# RPS_ARMOR_PCB_2022_V1_1.net
KiCad netlist of a schematic drawn in Altium Designer
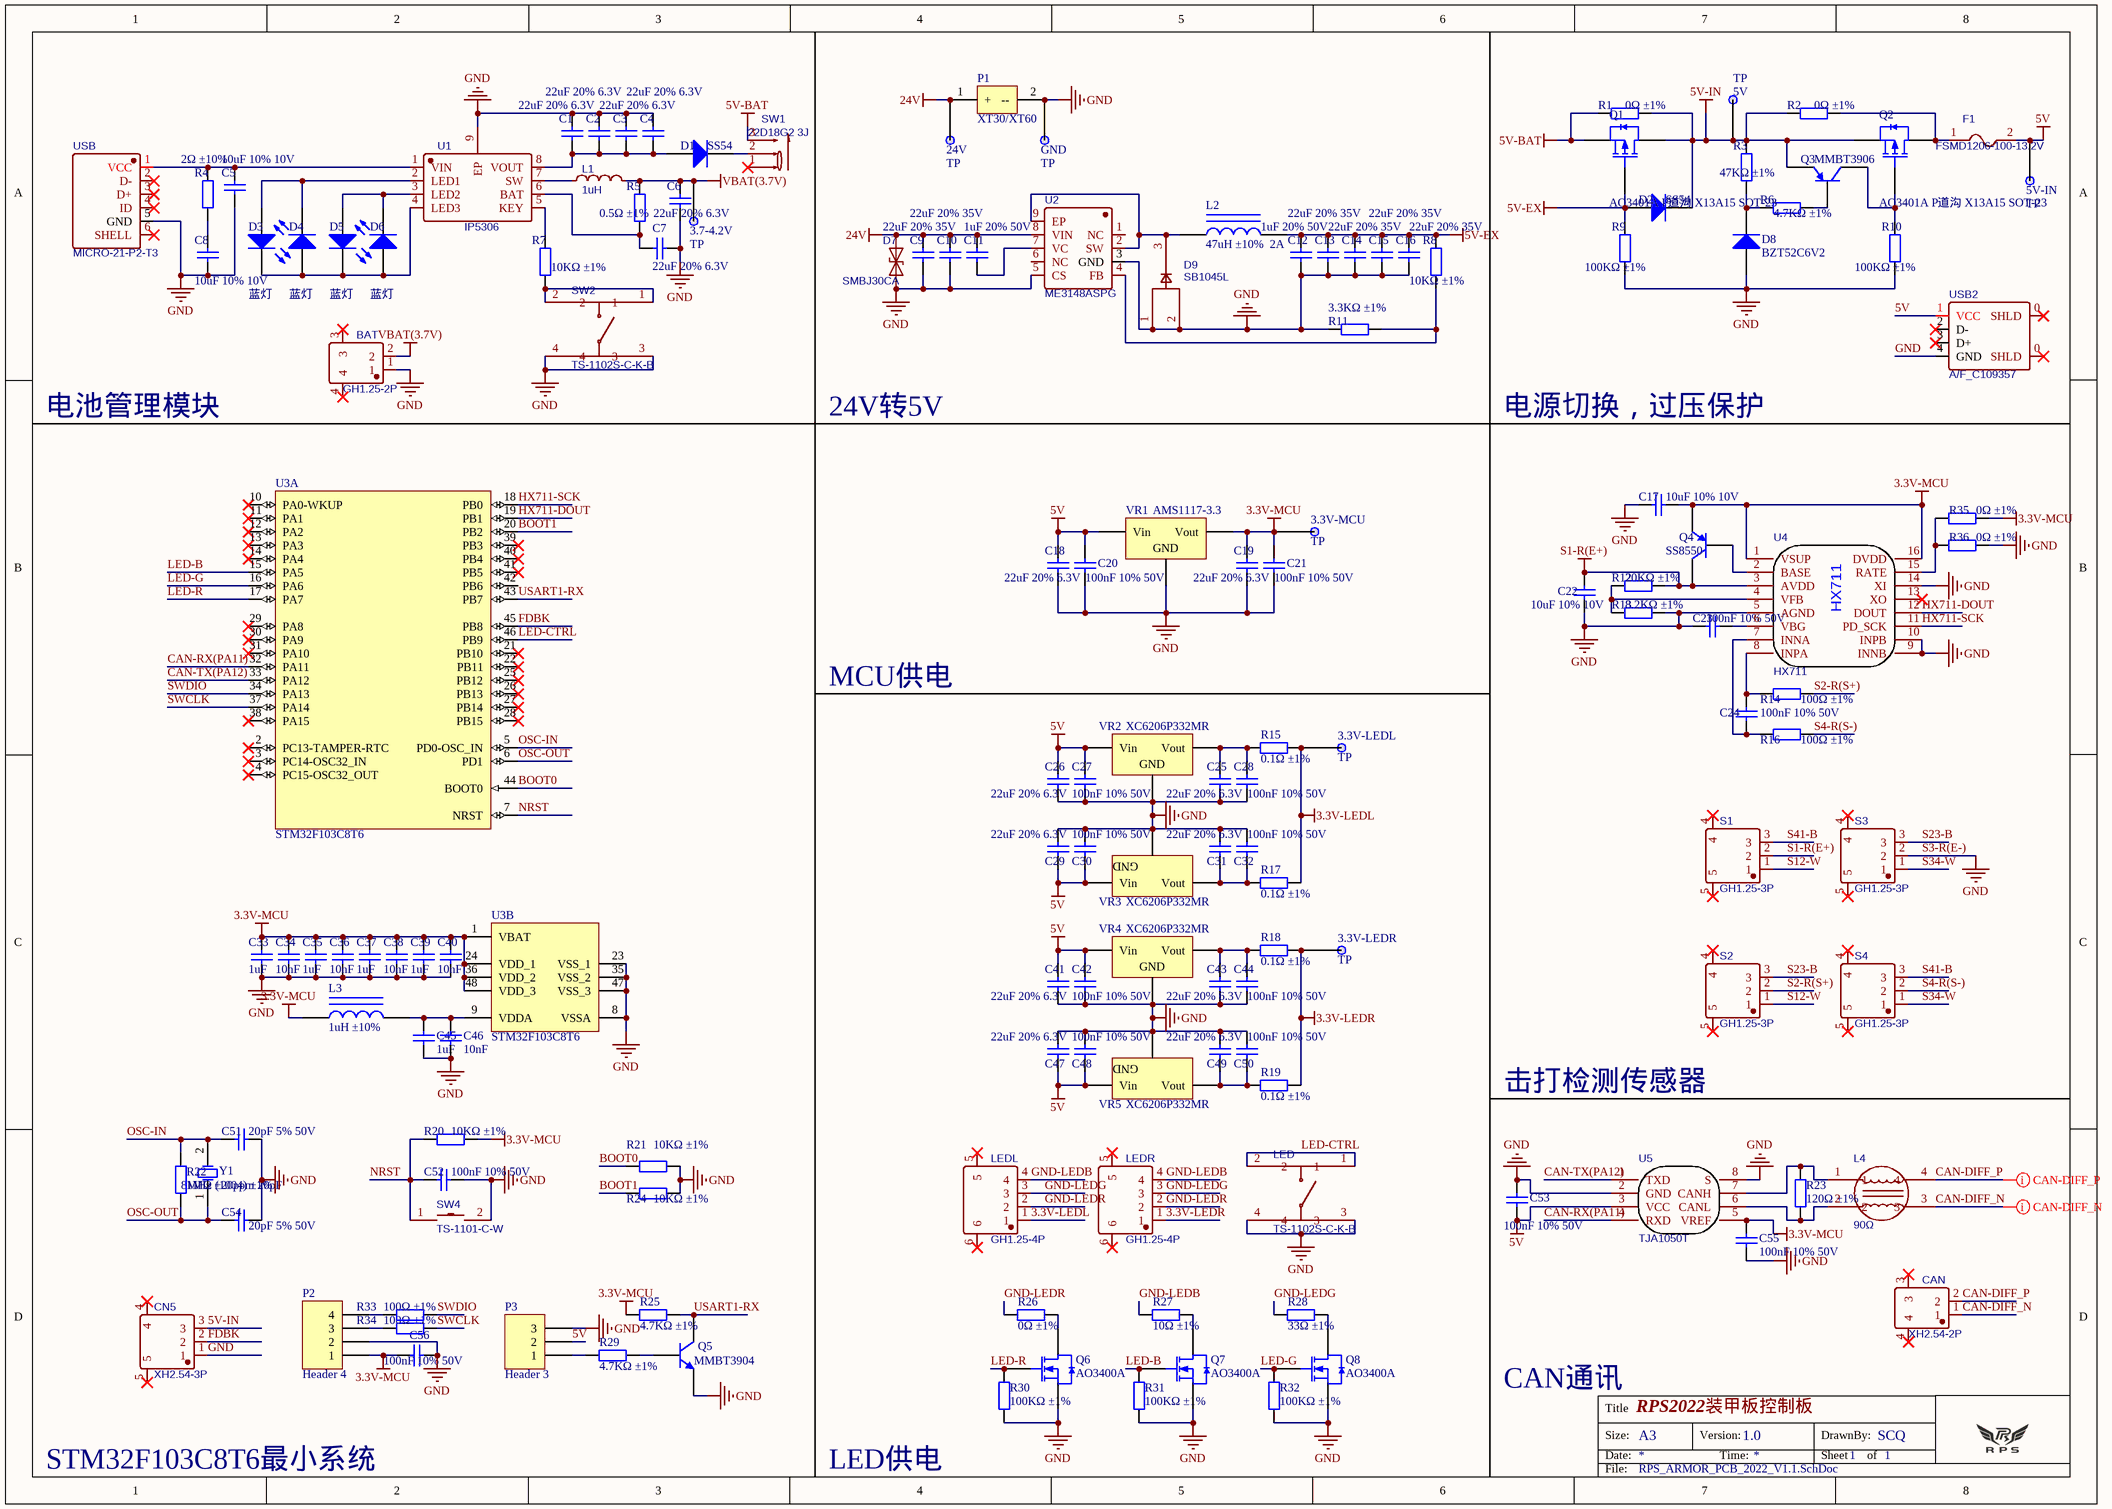
[diagram p0: RPS_ARMOR_PCB_2022_V1.1.SchDoc]

(export (version "E")
  (design (tool "Eeschema 10.0.6"))
  (components
    (comp (ref "3.3V-LEDL")
      (value "TP")
      (footprint "TP")
      (description "测试点")
      (libsource (lib "RPS_ARMOR_PCB_2022_V1.0") (part "TP"))
    )
    (comp (ref "3.3V-LEDR")
      (value "TP")
      (footprint "TP")
      (description "测试点")
      (libsource (lib "RPS_ARMOR_PCB_2022_V1.0") (part "TP"))
    )
    (comp (ref "3.3V-MCU")
      (value "TP")
      (footprint "TP")
      (description "测试点")
      (libsource (lib "RPS_ARMOR_PCB_2022_V1.0") (part "TP"))
    )
    (comp (ref "3.7-4.2V")
      (value "TP")
      (footprint "TP")
      (description "测试点")
      (libsource (lib "RPS_ARMOR_PCB_2022_V1.0") (part "TP"))
    )
    (comp (ref "5V")
      (value "TP")
      (footprint "TP")
      (description "测试点")
      (libsource (lib "RPS_ARMOR_PCB_2022_V1.0") (part "TP"))
    )
    (comp (ref "5V-IN")
      (value "TP")
      (footprint "TP")
      (description "测试点")
      (libsource (lib "RPS_ARMOR_PCB_2022_V1.0") (part "TP"))
    )
    (comp (ref "24V")
      (value "TP")
      (footprint "TP")
      (description "测试点")
      (libsource (lib "RPS_ARMOR_PCB_2022_V1.0") (part "TP"))
    )
    (comp (ref "BAT")
      (value "GH1.25-2P")
      (footprint "GH1.25-WS-2P")
      (description "GH1.25端子")
      (fields
        (field (name "BOM_SUPPLIER PART") "C225125")
        (field (name "BOM_MANUFACTURER PART") "A1257WR-S-2P")
        (field (name "CONTRIBUTOR") "LCSC")
      )
      (libsource (lib "RPS_ARMOR_PCB_2022_V1.0") (part "GH1.25-2P"))
    )
    (comp (ref "C1")
      (value "22uF 20% 6.3V")
      (footprint "0603_C")
      (description "C109448")
      (libsource (lib "Miscellaneous Devices LC") (part "0603 22uF (226) 20% 6.3V"))
    )
    (comp (ref "C2")
      (value "22uF 20% 6.3V")
      (footprint "0603_C")
      (description "C109448")
      (libsource (lib "Miscellaneous Devices LC") (part "0603 22uF (226) 20% 6.3V"))
    )
    (comp (ref "C3")
      (value "22uF 20% 6.3V")
      (footprint "0603_C")
      (description "C109448")
      (libsource (lib "Miscellaneous Devices LC") (part "0603 22uF (226) 20% 6.3V"))
    )
    (comp (ref "C4")
      (value "22uF 20% 6.3V")
      (footprint "0603_C")
      (description "C109448")
      (libsource (lib "Miscellaneous Devices LC") (part "0603 22uF (226) 20% 6.3V"))
    )
    (comp (ref "C5")
      (value "10uF 10% 10V")
      (footprint "0603_C")
      (description "C19702")
      (libsource (lib "Miscellaneous Devices LC") (part "0603 10uF (106) 10% 10V"))
    )
    (comp (ref "C6")
      (value "22uF 20% 6.3V")
      (footprint "0603_C")
      (description "C109448")
      (libsource (lib "Miscellaneous Devices LC") (part "0603 22uF (226) 20% 6.3V"))
    )
    (comp (ref "C7")
      (value "22uF 20% 6.3V")
      (footprint "0603_C")
      (description "C109448")
      (libsource (lib "Miscellaneous Devices LC") (part "0603 22uF (226) 20% 6.3V"))
    )
    (comp (ref "C8")
      (value "10uF 10% 10V")
      (footprint "0603_C")
      (description "C19702")
      (libsource (lib "Miscellaneous Devices LC") (part "0603 10uF (106) 10% 10V"))
    )
    (comp (ref "C9")
      (value "22uF 20% 35V")
      (footprint "1206_C")
      (description "C2835503")
      (libsource (lib "Miscellaneous Devices LC") (part "1206 10uF (106) 10% 50V"))
    )
    (comp (ref "C10")
      (value "22uF 20% 35V")
      (footprint "1206_C")
      (description "C2835503")
      (libsource (lib "Miscellaneous Devices LC") (part "1206 10uF (106) 10% 50V"))
    )
    (comp (ref "C11")
      (value "1uF 20% 50V")
      (footprint "0805_C")
      (description "C2217678")
      (libsource (lib "Miscellaneous Devices LC") (part "0805 1uF (105) 10% 50V"))
    )
    (comp (ref "C12")
      (value "1uF 20% 50V")
      (footprint "0805_C")
      (description "C2217678")
      (libsource (lib "Miscellaneous Devices LC") (part "0805 1uF (105) 10% 50V"))
    )
    (comp (ref "C13")
      (value "22uF 20% 35V")
      (footprint "1206_C")
      (description "C2835503")
      (libsource (lib "Miscellaneous Devices LC") (part "1206 10uF (106) 10% 50V"))
    )
    (comp (ref "C14")
      (value "22uF 20% 35V")
      (footprint "1206_C")
      (description "C2835503")
      (libsource (lib "Miscellaneous Devices LC") (part "1206 10uF (106) 10% 50V"))
    )
    (comp (ref "C15")
      (value "22uF 20% 35V")
      (footprint "1206_C")
      (description "C2835503")
      (libsource (lib "Miscellaneous Devices LC") (part "1206 10uF (106) 10% 50V"))
    )
    (comp (ref "C16")
      (value "22uF 20% 35V")
      (footprint "1206_C")
      (description "C2835503")
      (libsource (lib "Miscellaneous Devices LC") (part "1206 10uF (106) 10% 50V"))
    )
    (comp (ref "C17")
      (value "10uF 10% 10V")
      (footprint "0603_C")
      (description "贴片电容")
      (libsource (lib "Miscellaneous Devices LC") (part "0603 10uF (106) 10% 10V"))
    )
    (comp (ref "C18")
      (value "22uF 20% 6.3V")
      (footprint "0603_C")
      (description "C109448")
      (libsource (lib "Miscellaneous Devices LC") (part "0603 22uF (226) 20% 6.3V"))
    )
    (comp (ref "C19")
      (value "22uF 20% 6.3V")
      (footprint "0603_C")
      (description "C109448")
      (libsource (lib "Miscellaneous Devices LC") (part "0603 22uF (226) 20% 6.3V"))
    )
    (comp (ref "C20")
      (value "100nF 10% 50V")
      (footprint "0603_C")
      (description "贴片电容")
      (libsource (lib "Miscellaneous Devices LC") (part "0603 100nF (104) 10% 50V"))
    )
    (comp (ref "C21")
      (value "100nF 10% 50V")
      (footprint "0603_C")
      (description "贴片电容")
      (libsource (lib "Miscellaneous Devices LC") (part "0603 100nF (104) 10% 50V"))
    )
    (comp (ref "C22")
      (value "10uF 10% 10V")
      (footprint "0603_C")
      (description "贴片电容")
      (libsource (lib "Miscellaneous Devices LC") (part "0603 10uF (106) 10% 10V"))
    )
    (comp (ref "C23")
      (value "100nF 10% 50V")
      (footprint "0603_C")
      (description "贴片电容")
      (libsource (lib "Miscellaneous Devices LC") (part "0603 100nF (104) 10% 50V"))
    )
    (comp (ref "C24")
      (value "100nF 10% 50V")
      (footprint "0603_C")
      (description "贴片电容")
      (libsource (lib "Miscellaneous Devices LC") (part "0603 100nF (104) 10% 50V"))
    )
    (comp (ref "C25")
      (value "22uF 20% 6.3V")
      (footprint "0603_C")
      (description "C109448")
      (libsource (lib "Miscellaneous Devices LC") (part "0603 22uF (226) 20% 6.3V"))
    )
    (comp (ref "C26")
      (value "22uF 20% 6.3V")
      (footprint "0603_C")
      (description "C109448")
      (libsource (lib "Miscellaneous Devices LC") (part "0603 22uF (226) 20% 6.3V"))
    )
    (comp (ref "C27")
      (value "100nF 10% 50V")
      (footprint "0603_C")
      (description "贴片电容")
      (libsource (lib "Miscellaneous Devices LC") (part "0603 100nF (104) 10% 50V"))
    )
    (comp (ref "C28")
      (value "100nF 10% 50V")
      (footprint "0603_C")
      (description "贴片电容")
      (libsource (lib "Miscellaneous Devices LC") (part "0603 100nF (104) 10% 50V"))
    )
    (comp (ref "C29")
      (value "22uF 20% 6.3V")
      (footprint "0603_C")
      (description "C109448")
      (libsource (lib "Miscellaneous Devices LC") (part "0603 22uF (226) 20% 6.3V"))
    )
    (comp (ref "C30")
      (value "100nF 10% 50V")
      (footprint "0603_C")
      (description "贴片电容")
      (libsource (lib "Miscellaneous Devices LC") (part "0603 100nF (104) 10% 50V"))
    )
    (comp (ref "C31")
      (value "22uF 20% 6.3V")
      (footprint "0603_C")
      (description "C109448")
      (libsource (lib "Miscellaneous Devices LC") (part "0603 22uF (226) 20% 6.3V"))
    )
    (comp (ref "C32")
      (value "100nF 10% 50V")
      (footprint "0603_C")
      (description "贴片电容")
      (libsource (lib "Miscellaneous Devices LC") (part "0603 100nF (104) 10% 50V"))
    )
    (comp (ref "C33")
      (value "1uF")
      (footprint "0603_C")
      (description "贴片电容")
      (libsource (lib "Miscellaneous Devices LC") (part "0603 1uF (105) 10% 50V"))
    )
    (comp (ref "C34")
      (value "10nF")
      (footprint "0603_C")
      (description "贴片电容")
      (libsource (lib "Miscellaneous Devices LC") (part "0603 10nF (103) 10% 50V"))
    )
    (comp (ref "C35")
      (value "1uF")
      (footprint "0603_C")
      (description "贴片电容")
      (libsource (lib "Miscellaneous Devices LC") (part "0603 1uF (105) 10% 50V"))
    )
    (comp (ref "C36")
      (value "10nF")
      (footprint "0603_C")
      (description "贴片电容")
      (libsource (lib "Miscellaneous Devices LC") (part "0603 10nF (103) 10% 50V"))
    )
    (comp (ref "C37")
      (value "1uF")
      (footprint "0603_C")
      (description "贴片电容")
      (libsource (lib "Miscellaneous Devices LC") (part "0603 1uF (105) 10% 50V"))
    )
    (comp (ref "C38")
      (value "10nF")
      (footprint "0603_C")
      (description "贴片电容")
      (libsource (lib "Miscellaneous Devices LC") (part "0603 10nF (103) 10% 50V"))
    )
    (comp (ref "C39")
      (value "1uF")
      (footprint "0603_C")
      (description "贴片电容")
      (libsource (lib "Miscellaneous Devices LC") (part "0603 1uF (105) 10% 50V"))
    )
    (comp (ref "C40")
      (value "10nF")
      (footprint "0603_C")
      (description "贴片电容")
      (libsource (lib "Miscellaneous Devices LC") (part "0603 10nF (103) 10% 50V"))
    )
    (comp (ref "C41")
      (value "22uF 20% 6.3V")
      (footprint "0603_C")
      (description "C109448")
      (libsource (lib "Miscellaneous Devices LC") (part "0603 22uF (226) 20% 6.3V"))
    )
    (comp (ref "C42")
      (value "100nF 10% 50V")
      (footprint "0603_C")
      (description "贴片电容")
      (libsource (lib "Miscellaneous Devices LC") (part "0603 100nF (104) 10% 50V"))
    )
    (comp (ref "C43")
      (value "22uF 20% 6.3V")
      (footprint "0603_C")
      (description "C109448")
      (libsource (lib "Miscellaneous Devices LC") (part "0603 22uF (226) 20% 6.3V"))
    )
    (comp (ref "C44")
      (value "100nF 10% 50V")
      (footprint "0603_C")
      (description "贴片电容")
      (libsource (lib "Miscellaneous Devices LC") (part "0603 100nF (104) 10% 50V"))
    )
    (comp (ref "C45")
      (value "1uF")
      (footprint "0603_C")
      (description "贴片电容")
      (libsource (lib "Miscellaneous Devices LC") (part "0603 1uF (105) 10% 50V"))
    )
    (comp (ref "C46")
      (value "10nF")
      (footprint "0603_C")
      (description "贴片电容")
      (libsource (lib "Miscellaneous Devices LC") (part "0603 10nF (103) 10% 50V"))
    )
    (comp (ref "C47")
      (value "22uF 20% 6.3V")
      (footprint "0603_C")
      (description "C109448")
      (libsource (lib "Miscellaneous Devices LC") (part "0603 22uF (226) 20% 6.3V"))
    )
    (comp (ref "C48")
      (value "100nF 10% 50V")
      (footprint "0603_C")
      (description "贴片电容")
      (libsource (lib "Miscellaneous Devices LC") (part "0603 100nF (104) 10% 50V"))
    )
    (comp (ref "C49")
      (value "22uF 20% 6.3V")
      (footprint "0603_C")
      (description "C109448")
      (libsource (lib "Miscellaneous Devices LC") (part "0603 22uF (226) 20% 6.3V"))
    )
    (comp (ref "C50")
      (value "100nF 10% 50V")
      (footprint "0603_C")
      (description "贴片电容")
      (libsource (lib "Miscellaneous Devices LC") (part "0603 100nF (104) 10% 50V"))
    )
    (comp (ref "C51")
      (value "20pF 5% 50V")
      (footprint "0603_C")
      (description "贴片电容")
      (libsource (lib "Miscellaneous Devices LC") (part "0603 20pF (200) 5% 50V"))
    )
    (comp (ref "C52")
      (value "100nF 10% 50V")
      (footprint "0603_C")
      (description "贴片电容")
      (libsource (lib "Miscellaneous Devices LC") (part "0603 100nF (104) 10% 50V"))
    )
    (comp (ref "C53")
      (value "100nF 10% 50V")
      (footprint "0603_C")
      (description "贴片电容")
      (libsource (lib "Miscellaneous Devices LC") (part "0603 100nF (104) 10% 50V"))
    )
    (comp (ref "C54")
      (value "20pF 5% 50V")
      (footprint "0603_C")
      (description "贴片电容")
      (libsource (lib "Miscellaneous Devices LC") (part "0603 20pF (200) 5% 50V"))
    )
    (comp (ref "C55")
      (value "100nF 10% 50V")
      (footprint "0603_C")
      (description "贴片电容")
      (libsource (lib "Miscellaneous Devices LC") (part "0603 100nF (104) 10% 50V"))
    )
    (comp (ref "C56")
      (value "100nF 10% 50V")
      (footprint "0603_C")
      (description "贴片电容")
      (libsource (lib "Miscellaneous Devices LC") (part "0603 100nF (104) 10% 50V"))
    )
    (comp (ref "CAN")
      (value "XH2.54-2P")
      (footprint "XH2.54-LS-2P")
      (description "XH2.54端子")
      (fields
        (field (name "BOM_SUPPLIER PART") "C225125")
        (field (name "BOM_MANUFACTURER PART") "A1257WR-S-2P")
        (field (name "CONTRIBUTOR") "LCSC")
      )
      (libsource (lib "RPS_ARMOR_PCB_2022_V1.0") (part "GH1.25-2P"))
    )
    (comp (ref "CN5")
      (value "XH2.54-3P")
      (footprint "XH2.54-LS-3P")
      (description "XH2.54端子")
      (fields
        (field (name "BOM_SUPPLIER PART") "C225119")
        (field (name "BOM_MANUFACTURER PART") "A1257WV-S-3P")
        (field (name "CONTRIBUTOR") "LCSC")
      )
      (libsource (lib "RPS_ARMOR_PCB_2022_V1.0") (part "GH1.25-3P"))
    )
    (comp (ref "D1")
      (value "SS54")
      (footprint "SMA(DO-214AC)_S1")
      (description "C408258")
      (libsource (lib "Miscellaneous Devices LC") (part "SMA(DO-214AC) SS54"))
    )
    (comp (ref "D2")
      (value "SS54")
      (footprint "SMA(DO-214AC)_S1")
      (description "C408258")
      (libsource (lib "Miscellaneous Devices LC") (part "SMA(DO-214AC) SS54"))
    )
    (comp (ref "D3")
      (value "蓝灯")
      (footprint "0603_LED_S1")
      (description "发光二极管")
      (libsource (lib "Miscellaneous Devices LC") (part "0603 蓝灯"))
    )
    (comp (ref "D4")
      (value "蓝灯")
      (footprint "0603_LED_S1")
      (description "发光二极管")
      (libsource (lib "Miscellaneous Devices LC") (part "0603 蓝灯"))
    )
    (comp (ref "D5")
      (value "蓝灯")
      (footprint "0603_LED_S1")
      (description "发光二极管")
      (libsource (lib "Miscellaneous Devices LC") (part "0603 蓝灯"))
    )
    (comp (ref "D6")
      (value "蓝灯")
      (footprint "0603_LED_S1")
      (description "发光二极管")
      (libsource (lib "Miscellaneous Devices LC") (part "0603 蓝灯"))
    )
    (comp (ref "D7")
      (value "SMBJ30CA")
      (footprint "SMB_L4.6-W3.6-LS5.3-BI")
      (description "C78418")
      (libsource (lib "RPS_ARMOR_PCB_2022_V1.0") (part "SMBJ30CA-C78418"))
    )
    (comp (ref "D8")
      (value "BZT52C6V2")
      (footprint "SOD-123")
      (description "C699157稳压二极管")
      (libsource (lib "Miscellaneous Devices LC") (part "SOD-123 B5819W  SL"))
    )
    (comp (ref "D9")
      (value "SB1045L")
      (footprint "TO-277A_L4.7-W6.1-LS6.6-TR")
      (description "C113945")
      (fields (field (name "CONTRIBUTOR") "LCSC"))
      (libsource (lib "RPS_ARMOR_PCB_2022_V1.0") (part "SB1045L"))
    )
    (comp (ref "F1")
      (value "FSMD1206-100-13.2V")
      (footprint "F1206")
      (description "C883130")
      (fields
        (field (name "BOM_SUPPLIER PART") "C914093")
        (field (name "BOM_MANUFACTURER PART") "BSMD0603L-110")
        (field (name "CONTRIBUTOR") "LCSC")
      )
      (libsource (lib "RPS_ARMOR_PCB_2022_V1.0") (part "FSMD"))
    )
    (comp (ref "GND")
      (value "TP")
      (footprint "TP")
      (description "测试点")
      (libsource (lib "RPS_ARMOR_PCB_2022_V1.0") (part "TP"))
    )
    (comp (ref "L1")
      (value "1uH")
      (footprint "IND-SMD_L7.1-W6.6")
      (description "C87572")
      (fields (field (name "BOM_MANUFACTURER PART") "SPM6530T-1R0M120"))
      (libsource (lib "RPS_ARMOR_PCB_2022_V1.0") (part "1uH"))
    )
    (comp (ref "L2")
      (value "47uH ±10%  2A")
      (footprint "IND-SMD_L7.1-W6.6")
      (description "C149588")
      (libsource (lib "Miscellaneous Devices LC") (part "0805 47uH 10%"))
    )
    (comp (ref "L3")
      (value "1uH ±10%")
      (footprint "0805_L")
      (description "C1042")
      (libsource (lib "Miscellaneous Devices LC") (part "0805 1uH 10%"))
    )
    (comp (ref "L4")
      (value "90Ω")
      (footprint "FILTER-SMD_4P-L2.0-W1.2-BL")
      (description "C307642")
      (fields
        (field (name "BOM_MANUFACTURER PART") "ACM2012H-900-2P-T00")
        (field (name "BOM_SUPPLIER PART") "C76575")
      )
      (libsource (lib "RPS_ARMOR_PCB_2022_V1.0") (part "90Ω @100MHz"))
    )
    (comp (ref "LED")
      (value "TS-1102S-C-K-B")
      (footprint "TSW SMD-6*6*8")
      (description "C136667")
      (fields (field (name "BOM_SUPPLIER PART") "C381049") (field (name "CONTRIBUTOR") "LCSC"))
      (libsource (lib "RPS_ARMOR_PCB_2022_V1.0") (part "TS-1102S-C-K-B"))
    )
    (comp (ref "LEDL")
      (value "GH1.25-4P")
      (footprint "GH1.25-WS-4P")
      (description "GH1.25端子")
      (fields
        (field (name "BOM_SUPPLIER PART") "C225120")
        (field (name "BOM_MANUFACTURER PART") "A1257WV-S-4P")
        (field (name "CONTRIBUTOR") "LCSC")
      )
      (libsource (lib "RPS_ARMOR_PCB_2022_V1.0") (part "GH1.25-4P"))
    )
    (comp (ref "LEDR")
      (value "GH1.25-4P")
      (footprint "GH1.25-WS-4P")
      (description "GH1.25端子")
      (fields
        (field (name "BOM_SUPPLIER PART") "C225120")
        (field (name "BOM_MANUFACTURER PART") "A1257WV-S-4P")
        (field (name "CONTRIBUTOR") "LCSC")
      )
      (libsource (lib "RPS_ARMOR_PCB_2022_V1.0") (part "GH1.25-4P"))
    )
    (comp (ref "P1")
      (value "XT30/XT60")
      (footprint "XT30UPB-M")
      (description "XT端子")
      (libsource (lib "RPS_ARMOR_PCB_2022_V1.0") (part "XT30/XT60"))
    )
    (comp (ref "P2")
      (value "Header 4")
      (footprint "HDR2.54-LI-4P")
      (description "Header, 4-Pin")
      (fields (field (name "PUBLISHER") "Altium Limited"))
      (libsource (lib "Miscellaneous Connectors") (part "Header 4"))
    )
    (comp (ref "P3")
      (value "Header 3")
      (footprint "HDR2.54-LI-3P")
      (description "Header, 3-Pin")
      (fields (field (name "PUBLISHER") "Altium Limited"))
      (libsource (lib "Miscellaneous Connectors") (part "Header 3"))
    )
    (comp (ref "Q1")
      (value "AO3401A P道沟 X13A15 SOT-23")
      (footprint "SOT-23-3L")
      (description "MOS(场效应管)")
      (libsource (lib "Miscellaneous Devices LC") (part "AO3401A P道沟 X13A15 SOT-23"))
    )
    (comp (ref "Q2")
      (value "AO3401A P道沟 X13A15 SOT-23")
      (footprint "SOT-23-3L")
      (description "MOS(场效应管)")
      (libsource (lib "Miscellaneous Devices LC") (part "AO3401A P道沟 X13A15 SOT-23"))
    )
    (comp (ref "Q3")
      (value "MMBT3906")
      (footprint "SOT-23(SOT-23-3)")
      (description "C53444 三极管")
      (libsource (lib "Miscellaneous Devices LC") (part "SOT-23 MMBT5401 2L"))
    )
    (comp (ref "Q4")
      (value "SS8550")
      (footprint "SOT-23(SOT-23-3)")
      (description "C8542")
      (libsource (lib "Miscellaneous Devices LC") (part "SOT-23 SS8550 Y2"))
    )
    (comp (ref "Q5")
      (value "MMBT3904")
      (footprint "SOT-23(SOT-23-3)")
      (description "C20526三极管")
      (libsource (lib "Miscellaneous Devices LC") (part "SOT-23 MMBT5551  G1"))
    )
    (comp (ref "Q6")
      (value "AO3400A")
      (footprint "SOT-23-3L")
      (description "MOS(场效应管)")
      (libsource (lib "Miscellaneous Devices LC") (part "AO3400A N道沟 X0YV1T SOT-23"))
    )
    (comp (ref "Q7")
      (value "AO3400A")
      (footprint "SOT-23-3L")
      (description "MOS(场效应管)")
      (libsource (lib "Miscellaneous Devices LC") (part "AO3400A N道沟 X0YV1T SOT-23"))
    )
    (comp (ref "Q8")
      (value "AO3400A")
      (footprint "SOT-23-3L")
      (description "MOS(场效应管)")
      (libsource (lib "Miscellaneous Devices LC") (part "AO3400A N道沟 X0YV1T SOT-23"))
    )
    (comp (ref "R1")
      (value "0Ω ±1%")
      (footprint "0402_R")
      (description "贴片电阻")
      (libsource (lib "Miscellaneous Devices LC") (part "0402 0Ω (0R0) 1%"))
    )
    (comp (ref "R2")
      (value "0Ω ±1%")
      (footprint "0402_R")
      (description "贴片电阻")
      (libsource (lib "Miscellaneous Devices LC") (part "0402 0Ω (0R0) 1%"))
    )
    (comp (ref "R3")
      (value "47KΩ ±1%")
      (footprint "0603_R")
      (description "贴片电阻")
      (libsource (lib "Miscellaneous Devices LC") (part "0603 47KΩ (4702) 1%"))
    )
    (comp (ref "R4")
      (value "2Ω ±10%")
      (footprint "0603_R")
      (description "C25225")
      (libsource (lib "Miscellaneous Devices LC") (part "0603 1Ω (1R00) 1%"))
    )
    (comp (ref "R5")
      (value "0.5Ω ±1%")
      (footprint "1206_R")
      (description "C104947")
      (libsource (lib "Miscellaneous Devices LC") (part "1206 0.1Ω (R100) 1%"))
    )
    (comp (ref "R6")
      (value "4.7KΩ ±1%")
      (footprint "0603_R")
      (description "贴片电阻")
      (libsource (lib "Miscellaneous Devices LC") (part "0603 4.7KΩ (4701) 1%"))
    )
    (comp (ref "R7")
      (value "10KΩ ±1%")
      (footprint "0603_R")
      (description "贴片电阻")
      (libsource (lib "") (part "0603 10KΩ (1002) 1%_1"))
    )
    (comp (ref "R8")
      (value "10KΩ ±1%")
      (footprint "0603_R")
      (description "贴片电阻")
      (libsource (lib "") (part "0603 10KΩ (1002) 1%_1"))
    )
    (comp (ref "R9")
      (value "100KΩ ±1%")
      (footprint "0603_R")
      (description "贴片电阻")
      (libsource (lib "Miscellaneous Devices LC") (part "0603 100KΩ (1003) 1%"))
    )
    (comp (ref "R10")
      (value "100KΩ ±1%")
      (footprint "0603_R")
      (description "贴片电阻")
      (libsource (lib "Miscellaneous Devices LC") (part "0603 100KΩ (1003) 1%"))
    )
    (comp (ref "R11")
      (value "3.3KΩ ±1%")
      (footprint "0603_R")
      (description "贴片电阻")
      (libsource (lib "Miscellaneous Devices LC") (part "0603 3.3KΩ (3301) 1%"))
    )
    (comp (ref "R12")
      (value "20KΩ ±1%")
      (footprint "0603_R")
      (description "C4184")
      (libsource (lib "Miscellaneous Devices LC") (part "0603 20KΩ (2002) 1%"))
    )
    (comp (ref "R13")
      (value "8.2KΩ ±1%")
      (footprint "0603_R")
      (description "C25981")
      (libsource (lib "Miscellaneous Devices LC") (part "0603 8.2KΩ (8201) 1%"))
    )
    (comp (ref "R14")
      (value "100Ω ±1%")
      (footprint "0603_R")
      (description "贴片电阻")
      (libsource (lib "Miscellaneous Devices LC") (part "0603 100Ω (1000) 1%"))
    )
    (comp (ref "R15")
      (value "0.1Ω ±1%")
      (footprint "1206_R")
      (description "贴片电阻")
      (libsource (lib "") (part "1206 0.1Ω (R100) 1%_1"))
    )
    (comp (ref "R16")
      (value "100Ω ±1%")
      (footprint "0603_R")
      (description "贴片电阻")
      (libsource (lib "Miscellaneous Devices LC") (part "0603 100Ω (1000) 1%"))
    )
    (comp (ref "R17")
      (value "0.1Ω ±1%")
      (footprint "1206_R")
      (description "贴片电阻")
      (libsource (lib "") (part "1206 0.1Ω (R100) 1%_1"))
    )
    (comp (ref "R18")
      (value "0.1Ω ±1%")
      (footprint "1206_R")
      (description "贴片电阻")
      (libsource (lib "") (part "1206 0.1Ω (R100) 1%_1"))
    )
    (comp (ref "R19")
      (value "0.1Ω ±1%")
      (footprint "1206_R")
      (description "贴片电阻")
      (libsource (lib "") (part "1206 0.1Ω (R100) 1%_1"))
    )
    (comp (ref "R20")
      (value "10KΩ ±1%")
      (footprint "0603_R")
      (description "贴片电阻")
      (libsource (lib "Miscellaneous Devices LC") (part "0603 10KΩ (1002) 1%"))
    )
    (comp (ref "R21")
      (value "10KΩ ±1%")
      (footprint "0603_R")
      (description "贴片电阻")
      (libsource (lib "Miscellaneous Devices LC") (part "0603 10KΩ (1002) 1%"))
    )
    (comp (ref "R22")
      (value "1MΩ (1004) ±1%")
      (footprint "0603_R")
      (description "贴片电阻")
      (libsource (lib "Miscellaneous Devices LC") (part "0603 1MΩ (1004) 1%"))
    )
    (comp (ref "R23")
      (value "120Ω ±1%")
      (footprint "0603_R")
      (description "贴片电阻")
      (libsource (lib "Miscellaneous Devices LC") (part "0603 120Ω (1200) 1%"))
    )
    (comp (ref "R24")
      (value "10KΩ ±1%")
      (footprint "0603_R")
      (description "贴片电阻")
      (libsource (lib "Miscellaneous Devices LC") (part "0603 10KΩ (1002) 1%"))
    )
    (comp (ref "R25")
      (value "4.7KΩ ±1%")
      (footprint "0603_R")
      (description "贴片电阻")
      (libsource (lib "Miscellaneous Devices LC") (part "0603 4.7KΩ (4701) 1%"))
    )
    (comp (ref "R26")
      (value "0Ω ±1%")
      (footprint "0603_R")
      (description "贴片电阻")
      (libsource (lib "Miscellaneous Devices LC") (part "0603 1KΩ (1001) 1%"))
    )
    (comp (ref "R27")
      (value "10Ω ±1%")
      (footprint "0603_R")
      (description "贴片电阻")
      (libsource (lib "Miscellaneous Devices LC") (part "0603 1KΩ (1001) 1%"))
    )
    (comp (ref "R28")
      (value "33Ω ±1%")
      (footprint "0603_R")
      (description "贴片电阻")
      (libsource (lib "Miscellaneous Devices LC") (part "0603 1KΩ (1001) 1%"))
    )
    (comp (ref "R29")
      (value "4.7KΩ ±1%")
      (footprint "0603_R")
      (description "贴片电阻")
      (libsource (lib "Miscellaneous Devices LC") (part "0603 4.7KΩ (4701) 1%"))
    )
    (comp (ref "R30")
      (value "100KΩ ±1%")
      (footprint "0603_R")
      (description "贴片电阻")
      (libsource (lib "Miscellaneous Devices LC") (part "0603 100KΩ (1003) 1%"))
    )
    (comp (ref "R31")
      (value "100KΩ ±1%")
      (footprint "0603_R")
      (description "贴片电阻")
      (libsource (lib "Miscellaneous Devices LC") (part "0603 100KΩ (1003) 1%"))
    )
    (comp (ref "R32")
      (value "100KΩ ±1%")
      (footprint "0603_R")
      (description "贴片电阻")
      (libsource (lib "Miscellaneous Devices LC") (part "0603 100KΩ (1003) 1%"))
    )
    (comp (ref "R33")
      (value "100Ω ±1%")
      (footprint "0603_R")
      (description "贴片电阻")
      (libsource (lib "Miscellaneous Devices LC") (part "0603 100Ω (1000) 1%"))
    )
    (comp (ref "R34")
      (value "100Ω ±1%")
      (footprint "0603_R")
      (description "贴片电阻")
      (libsource (lib "Miscellaneous Devices LC") (part "0603 100Ω (1000) 1%"))
    )
    (comp (ref "R35")
      (value "0Ω ±1%")
      (footprint "0603_R")
      (description "贴片电阻")
      (libsource (lib "") (part "0603 0Ω (0R0) 1%_1"))
    )
    (comp (ref "R36")
      (value "0Ω ±1%")
      (footprint "0603_R")
      (description "贴片电阻")
      (libsource (lib "Miscellaneous Devices LC") (part "0603 0Ω (0R0) 1%"))
    )
    (comp (ref "S1")
      (value "GH1.25-3P")
      (footprint "GH1.25-WS-3P")
      (description "GH1.25端子")
      (fields
        (field (name "BOM_SUPPLIER PART") "C225119")
        (field (name "BOM_MANUFACTURER PART") "A1257WV-S-3P")
        (field (name "CONTRIBUTOR") "LCSC")
      )
      (libsource (lib "RPS_ARMOR_PCB_2022_V1.0") (part "GH1.25-3P"))
    )
    (comp (ref "S2")
      (value "GH1.25-3P")
      (footprint "GH1.25-WS-3P")
      (description "GH1.25端子")
      (fields
        (field (name "BOM_SUPPLIER PART") "C225119")
        (field (name "BOM_MANUFACTURER PART") "A1257WV-S-3P")
        (field (name "CONTRIBUTOR") "LCSC")
      )
      (libsource (lib "RPS_ARMOR_PCB_2022_V1.0") (part "GH1.25-3P"))
    )
    (comp (ref "S3")
      (value "GH1.25-3P")
      (footprint "GH1.25-WS-3P")
      (description "GH1.25端子")
      (fields
        (field (name "BOM_SUPPLIER PART") "C225119")
        (field (name "BOM_MANUFACTURER PART") "A1257WV-S-3P")
        (field (name "CONTRIBUTOR") "LCSC")
      )
      (libsource (lib "RPS_ARMOR_PCB_2022_V1.0") (part "GH1.25-3P"))
    )
    (comp (ref "S4")
      (value "GH1.25-3P")
      (footprint "GH1.25-WS-3P")
      (description "GH1.25端子")
      (fields
        (field (name "BOM_SUPPLIER PART") "C225119")
        (field (name "BOM_MANUFACTURER PART") "A1257WV-S-3P")
        (field (name "CONTRIBUTOR") "LCSC")
      )
      (libsource (lib "RPS_ARMOR_PCB_2022_V1.0") (part "GH1.25-3P"))
    )
    (comp (ref "SW1")
      (value "22D18G2 3J")
      (footprint "SW-SMD_MST-22D18G23J")
      (description "C514026")
      (fields
        (field (name "BOM_SUPPLIER PART") "C668586")
        (field (name "BOM_MANUFACTURER PART") "MST-22D18G2 3J")
        (field (name "CONTRIBUTOR") "LCSC")
      )
      (libsource (lib "器件库") (part "MST-22D18G2 3J"))
    )
    (comp (ref "SW2")
      (value "TS-1102S-C-K-B")
      (footprint "TSW SMD-6*6*8")
      (description "C136667")
      (fields (field (name "BOM_SUPPLIER PART") "C381049") (field (name "CONTRIBUTOR") "LCSC"))
      (libsource (lib "RPS_ARMOR_PCB_2022_V1.0") (part "TS-1102S-C-K-B"))
    )
    (comp (ref "SW4")
      (value "TS-1101-C-W")
      (footprint "SW-SMD_L6.0-W3.3-LS8.0")
      (description "C318938")
      (fields (field (name "CONTRIBUTOR") "LCSC"))
      (libsource (lib "RPS_ARMOR_PCB_2022_V1.0") (part "TS-1101-C-W"))
    )
    (comp (ref "U1")
      (value "IP5306")
      (footprint "ESOP-8_L4.9-W3.9-P1.27-LS6.0-BL-EP")
      (description "C181692")
      (fields (field (name "CONTRIBUTOR") "LCSC"))
      (libsource (lib "RPS_ARMOR_PCB_2022_V1.0") (part "IP5306"))
    )
    (comp (ref "U2")
      (value "ME3148ASPG")
      (footprint "ESOP-8_L4.9-W3.9-P1.27-LS6.0-BL-EP")
      (description "C2683415")
      (fields (field (name "CONTRIBUTOR") "LCSC"))
      (libsource (lib "RPS_ARMOR_PCB_2022_V1.0") (part "ME3148ASPG"))
    )
    (comp (ref "U3")
      (value "STM32F103C8T6")
      (footprint "LQFP-48_7x7x05P")
      (description "ARM")
      (libsource (lib "Miscellaneous Devices LC") (part "STM32F103C8T6"))
    )
    (comp (ref "U4")
      (value "HX711")
      (footprint "SOP16")
      (fields (field (name "BOM_SUPPLIER PART") "C43656"))
      (libsource (lib "RPS_ARMOR_PCB_2022_V1.0") (part "HX711"))
    )
    (comp (ref "U5")
      (value "TJA1050T")
      (footprint "SOIC-8_L5.0-W4.0-P1.27-LS6.0-BL")
      (description "C6952(C313021)")
      (fields
        (field (name "BOM_MANUFACTURER PART") "TJA1050T/CM,118")
        (field (name "BOM_SUPPLIER PART") "C6952")
      )
      (libsource (lib "RPS_ARMOR_PCB_2022_V1.0") (part "TJA1050T"))
    )
    (comp (ref "USB")
      (value "MICRO-21-P2-T3")
      (footprint "MICRO-USB-SMD_LI")
      (description "C2834965 Micro-B 母座 立贴")
      (fields (field (name "BOM_SUPPLIER PART") "C2834965") (field (name "CONTRIBUTOR") "LCSC"))
      (libsource (lib "RPS_ARMOR_PCB_2022_V1.0") (part "MICRO-USB-SMD_LI"))
    )
    (comp (ref "USB2")
      (value "A/F_C109357")
      (footprint "USB-A-TH_USB-A-F-1")
      (fields (field (name "BOM_SUPPLIER PART") "C109357") (field (name "CONTRIBUTOR") "立创EDA官方封装库"))
      (libsource (lib "RPS_ARMOR_PCB_2022_V1.0") (part "A/F_C109357"))
    )
    (comp (ref "VR1")
      (value "AMS1117-3.3")
      (footprint "SOT-223")
      (description "低压差线性稳压(LDO)")
      (libsource (lib "Miscellaneous Devices LC") (part "SOT-223 AMS1117-3.3"))
    )
    (comp (ref "VR2")
      (value "XC6206P332MR")
      (footprint "SOT-23-3L")
      (description "低压差线性稳压(LDO)")
      (libsource (lib "Miscellaneous Devices LC") (part "SOT-23 XC6206P332MR"))
    )
    (comp (ref "VR3")
      (value "XC6206P332MR")
      (footprint "SOT-23-3L")
      (description "低压差线性稳压(LDO)")
      (libsource (lib "") (part "SOT-23 XC6206P332MR_1"))
    )
    (comp (ref "VR4")
      (value "XC6206P332MR")
      (footprint "SOT-23-3L")
      (description "低压差线性稳压(LDO)")
      (libsource (lib "Miscellaneous Devices LC") (part "SOT-23 XC6206P332MR"))
    )
    (comp (ref "VR5")
      (value "XC6206P332MR")
      (footprint "SOT-23-3L")
      (description "低压差线性稳压(LDO)")
      (libsource (lib "") (part "SOT-23 XC6206P332MR_1"))
    )
    (comp (ref "Y1")
      (value "8MHz ±20ppm 20pF")
      (footprint "SMD-5032_2P")
      (description "贴片晶振")
      (libsource (lib "Miscellaneous Devices LC") (part "SMD-5032_2P 8MHz 20ppm 20pF"))
    )
  )
  (nets
    (net (code "1") (name "/BOOT0") (class "Default")
      (node (ref "R21") (pin "1") (pinfunction "1_1") (pintype "passive"))
      (node (ref "U3") (pin "44") (pinfunction "BOOT0_44") (pintype "input"))
    )
    (net (code "2") (name "/BOOT1") (class "Default")
      (node (ref "R24") (pin "1") (pinfunction "1_1") (pintype "passive"))
      (node (ref "U3") (pin "20") (pinfunction "PB2_20") (pintype "bidirectional"))
    )
    (net (code "3") (name "/CAN-DIFF_N") (class "Default")
      (node (ref "CAN") (pin "1") (pinfunction "1_1") (pintype "passive"))
      (node (ref "L4") (pin "3") (pinfunction "3_3") (pintype "passive"))
    )
    (net (code "4") (name "/CAN-DIFF_P") (class "Default")
      (node (ref "CAN") (pin "2") (pinfunction "2_2") (pintype "passive"))
      (node (ref "L4") (pin "4") (pinfunction "4_4") (pintype "passive"))
    )
    (net (code "5") (name "/CAN-RX(PA11)") (class "Default")
      (node (ref "U3") (pin "32") (pinfunction "PA11_32") (pintype "bidirectional"))
      (node (ref "U5") (pin "4") (pinfunction "RXD_4") (pintype "passive"))
    )
    (net (code "6") (name "/CAN-TX(PA12)") (class "Default")
      (node (ref "U3") (pin "33") (pinfunction "PA12_33") (pintype "bidirectional"))
      (node (ref "U5") (pin "1") (pinfunction "TXD_1") (pintype "passive"))
    )
    (net (code "7") (name "/FDBK") (class "Default")
      (node (ref "CN5") (pin "2") (pinfunction "2_2") (pintype "passive"))
      (node (ref "U3") (pin "45") (pinfunction "PB8_45") (pintype "bidirectional"))
    )
    (net (code "8") (name "/GND-LEDB") (class "Default")
      (node (ref "LEDL") (pin "4") (pinfunction "4_4") (pintype "passive"))
      (node (ref "LEDR") (pin "4") (pinfunction "4_4") (pintype "passive"))
      (node (ref "R27") (pin "2") (pinfunction "2_2") (pintype "passive"))
    )
    (net (code "9") (name "/GND-LEDG") (class "Default")
      (node (ref "LEDL") (pin "3") (pinfunction "3_3") (pintype "passive"))
      (node (ref "LEDR") (pin "3") (pinfunction "3_3") (pintype "passive"))
      (node (ref "R28") (pin "2") (pinfunction "2_2") (pintype "passive"))
    )
    (net (code "10") (name "/GND-LEDR") (class "Default")
      (node (ref "LEDL") (pin "2") (pinfunction "2_2") (pintype "passive"))
      (node (ref "LEDR") (pin "2") (pinfunction "2_2") (pintype "passive"))
      (node (ref "R26") (pin "2") (pinfunction "2_2") (pintype "passive"))
    )
    (net (code "11") (name "/HX711-DOUT") (class "Default")
      (node (ref "U3") (pin "19") (pinfunction "PB1_19") (pintype "bidirectional"))
      (node (ref "U4") (pin "12") (pinfunction "DOUT_12") (pintype "passive"))
    )
    (net (code "12") (name "/HX711-SCK") (class "Default")
      (node (ref "U3") (pin "18") (pinfunction "PB0_18") (pintype "bidirectional"))
      (node (ref "U4") (pin "11") (pinfunction "PD_SCK_11") (pintype "passive"))
    )
    (net (code "13") (name "/LED-B") (class "Default")
      (node (ref "Q7") (pin "1") (pinfunction "G_1") (pintype "passive"))
      (node (ref "R31") (pin "2") (pinfunction "2_2") (pintype "passive"))
      (node (ref "U3") (pin "15") (pinfunction "PA5_15") (pintype "bidirectional"))
    )
    (net (code "14") (name "/LED-CTRL") (class "Default")
      (node (ref "LED") (pin "1") (pinfunction "1_1") (pintype "passive"))
      (node (ref "LED") (pin "2") (pinfunction "2_2") (pintype "passive"))
      (node (ref "U3") (pin "46") (pinfunction "PB9_46") (pintype "bidirectional"))
    )
    (net (code "15") (name "/LED-G") (class "Default")
      (node (ref "Q8") (pin "1") (pinfunction "G_1") (pintype "passive"))
      (node (ref "R32") (pin "2") (pinfunction "2_2") (pintype "passive"))
      (node (ref "U3") (pin "16") (pinfunction "PA6_16") (pintype "bidirectional"))
    )
    (net (code "16") (name "/LED-R") (class "Default")
      (node (ref "Q6") (pin "1") (pinfunction "G_1") (pintype "passive"))
      (node (ref "R30") (pin "2") (pinfunction "2_2") (pintype "passive"))
      (node (ref "U3") (pin "17") (pinfunction "PA7_17") (pintype "bidirectional"))
    )
    (net (code "17") (name "/NRST") (class "Default")
      (node (ref "C52") (pin "1") (pinfunction "1_1") (pintype "passive"))
      (node (ref "R20") (pin "1") (pinfunction "1_1") (pintype "passive"))
      (node (ref "SW4") (pin "1") (pinfunction "1_1") (pintype "passive"))
      (node (ref "U3") (pin "7") (pinfunction "NRST_7") (pintype "bidirectional"))
    )
    (net (code "18") (name "/OSC-IN") (class "Default")
      (node (ref "C51") (pin "1") (pinfunction "1_1") (pintype "passive"))
      (node (ref "R22") (pin "2") (pinfunction "2_2") (pintype "passive"))
      (node (ref "U3") (pin "5") (pinfunction "PD0-OSC_IN_5") (pintype "bidirectional"))
      (node (ref "Y1") (pin "2") (pinfunction "OSC2_2") (pintype "passive"))
    )
    (net (code "19") (name "/OSC-OUT") (class "Default")
      (node (ref "C54") (pin "1") (pinfunction "1_1") (pintype "passive"))
      (node (ref "R22") (pin "1") (pinfunction "1_1") (pintype "passive"))
      (node (ref "U3") (pin "6") (pinfunction "PD1_6") (pintype "bidirectional"))
      (node (ref "Y1") (pin "1") (pinfunction "OSC1_1") (pintype "passive"))
    )
    (net (code "20") (name "/S2-R(S+)") (class "Default")
      (node (ref "R14") (pin "2") (pinfunction "2_2") (pintype "passive"))
      (node (ref "S2") (pin "2") (pinfunction "2_2") (pintype "passive"))
    )
    (net (code "21") (name "/S4-R(S-)") (class "Default")
      (node (ref "R16") (pin "2") (pinfunction "2_2") (pintype "passive"))
      (node (ref "S4") (pin "2") (pinfunction "2_2") (pintype "passive"))
    )
    (net (code "22") (name "/S12-W") (class "Default")
      (node (ref "S1") (pin "1") (pinfunction "1_1") (pintype "passive"))
      (node (ref "S2") (pin "1") (pinfunction "1_1") (pintype "passive"))
    )
    (net (code "23") (name "/S23-B") (class "Default")
      (node (ref "S2") (pin "3") (pinfunction "3_3") (pintype "passive"))
      (node (ref "S3") (pin "3") (pinfunction "3_3") (pintype "passive"))
    )
    (net (code "24") (name "/S34-W") (class "Default")
      (node (ref "S3") (pin "1") (pinfunction "1_1") (pintype "passive"))
      (node (ref "S4") (pin "1") (pinfunction "1_1") (pintype "passive"))
    )
    (net (code "25") (name "/S41-B") (class "Default")
      (node (ref "S1") (pin "3") (pinfunction "3_3") (pintype "passive"))
      (node (ref "S4") (pin "3") (pinfunction "3_3") (pintype "passive"))
    )
    (net (code "26") (name "/SWCLK") (class "Default")
      (node (ref "R34") (pin "2") (pinfunction "2_2") (pintype "passive"))
      (node (ref "U3") (pin "37") (pinfunction "PA14_37") (pintype "bidirectional"))
    )
    (net (code "27") (name "/SWDIO") (class "Default")
      (node (ref "R33") (pin "2") (pinfunction "2_2") (pintype "passive"))
      (node (ref "U3") (pin "34") (pinfunction "PA13_34") (pintype "bidirectional"))
    )
    (net (code "28") (name "/USART1-RX") (class "Default")
      (node (ref "Q5") (pin "3") (pinfunction "C_3") (pintype "passive"))
      (node (ref "R25") (pin "2") (pinfunction "2_2") (pintype "passive"))
      (node (ref "U3") (pin "43") (pinfunction "PB7_43") (pintype "bidirectional"))
    )
    (net (code "29") (name "3.3V-LEDL") (class "Default")
      (node (ref "3.3V-LEDL") (pin "1") (pinfunction "1_1") (pintype "passive"))
      (node (ref "LEDL") (pin "1") (pinfunction "1_1") (pintype "passive"))
      (node (ref "R15") (pin "2") (pinfunction "2_2") (pintype "passive"))
      (node (ref "R17") (pin "2") (pinfunction "2_2") (pintype "passive"))
    )
    (net (code "30") (name "3.3V-LEDR") (class "Default")
      (node (ref "3.3V-LEDR") (pin "1") (pinfunction "1_1") (pintype "passive"))
      (node (ref "LEDR") (pin "1") (pinfunction "1_1") (pintype "passive"))
      (node (ref "R18") (pin "2") (pinfunction "2_2") (pintype "passive"))
      (node (ref "R19") (pin "2") (pinfunction "2_2") (pintype "passive"))
    )
    (net (code "31") (name "3.3V-MCU") (class "Default")
      (node (ref "3.3V-MCU") (pin "1") (pinfunction "1_1") (pintype "passive"))
      (node (ref "C17") (pin "2") (pinfunction "2_2") (pintype "passive"))
      (node (ref "C19") (pin "2") (pinfunction "2_2") (pintype "passive"))
      (node (ref "C21") (pin "2") (pinfunction "2_2") (pintype "passive"))
      (node (ref "C33") (pin "2") (pinfunction "2_2") (pintype "passive"))
      (node (ref "C34") (pin "2") (pinfunction "2_2") (pintype "passive"))
      (node (ref "C35") (pin "2") (pinfunction "2_2") (pintype "passive"))
      (node (ref "C36") (pin "2") (pinfunction "2_2") (pintype "passive"))
      (node (ref "C37") (pin "2") (pinfunction "2_2") (pintype "passive"))
      (node (ref "C38") (pin "2") (pinfunction "2_2") (pintype "passive"))
      (node (ref "C39") (pin "2") (pinfunction "2_2") (pintype "passive"))
      (node (ref "C40") (pin "2") (pinfunction "2_2") (pintype "passive"))
      (node (ref "C55") (pin "2") (pinfunction "2_2") (pintype "passive"))
      (node (ref "C56") (pin "1") (pinfunction "1_1") (pintype "passive"))
      (node (ref "L3") (pin "1") (pinfunction "1_1") (pintype "passive"))
      (node (ref "P2") (pin "1") (pinfunction "1_1") (pintype "passive"))
      (node (ref "Q4") (pin "2") (pinfunction "E_2") (pintype "passive"))
      (node (ref "R20") (pin "2") (pinfunction "2_2") (pintype "passive"))
      (node (ref "R25") (pin "1") (pinfunction "1_1") (pintype "passive"))
      (node (ref "R35") (pin "1") (pinfunction "1_1") (pintype "passive"))
      (node (ref "U3") (pin "1") (pinfunction "VBAT_1") (pintype "power_in"))
      (node (ref "U3") (pin "24") (pinfunction "VDD_1_24") (pintype "power_in"))
      (node (ref "U3") (pin "36") (pinfunction "VDD_2_36") (pintype "power_in"))
      (node (ref "U3") (pin "48") (pinfunction "VDD_3_48") (pintype "power_in"))
      (node (ref "U4") (pin "1") (pinfunction "VSUP_1") (pintype "passive"))
      (node (ref "U4") (pin "16") (pinfunction "DVDD_16") (pintype "passive"))
      (node (ref "U5") (pin "5") (pinfunction "VREF_5") (pintype "passive"))
      (node (ref "VR1") (pin "2") (pinfunction "Vout_2") (pintype "passive"))
    )
    (net (code "32") (name "5V") (class "Default")
      (node (ref "5V-IN") (pin "1") (pinfunction "1_1") (pintype "passive"))
      (node (ref "C18") (pin "2") (pinfunction "2_2") (pintype "passive"))
      (node (ref "C20") (pin "2") (pinfunction "2_2") (pintype "passive"))
      (node (ref "C26") (pin "2") (pinfunction "2_2") (pintype "passive"))
      (node (ref "C27") (pin "2") (pinfunction "2_2") (pintype "passive"))
      (node (ref "C29") (pin "2") (pinfunction "2_2") (pintype "passive"))
      (node (ref "C30") (pin "2") (pinfunction "2_2") (pintype "passive"))
      (node (ref "C41") (pin "2") (pinfunction "2_2") (pintype "passive"))
      (node (ref "C42") (pin "2") (pinfunction "2_2") (pintype "passive"))
      (node (ref "C47") (pin "2") (pinfunction "2_2") (pintype "passive"))
      (node (ref "C48") (pin "2") (pinfunction "2_2") (pintype "passive"))
      (node (ref "C53") (pin "1") (pinfunction "1_1") (pintype "passive"))
      (node (ref "F1") (pin "2") (pinfunction "2_2") (pintype "passive"))
      (node (ref "P3") (pin "2") (pinfunction "2_2") (pintype "passive"))
      (node (ref "U5") (pin "3") (pinfunction "VCC_3") (pintype "passive"))
      (node (ref "USB2") (pin "1") (pinfunction "VCC_1") (pintype "passive"))
      (node (ref "VR1") (pin "3") (pinfunction "Vin_3") (pintype "passive"))
      (node (ref "VR2") (pin "3") (pinfunction "Vin_3") (pintype "passive"))
      (node (ref "VR3") (pin "3") (pinfunction "Vin_3") (pintype "passive"))
      (node (ref "VR4") (pin "3") (pinfunction "Vin_3") (pintype "passive"))
      (node (ref "VR5") (pin "3") (pinfunction "Vin_3") (pintype "passive"))
    )
    (net (code "33") (name "5V-BAT") (class "Default")
      (node (ref "Q1") (pin "2") (pinfunction "S_2") (pintype "passive"))
      (node (ref "R1") (pin "1") (pinfunction "1_1") (pintype "passive"))
      (node (ref "SW1") (pin "3") (pinfunction "3_3") (pintype "passive"))
    )
    (net (code "34") (name "5V-EX") (class "Default")
      (node (ref "C12") (pin "2") (pinfunction "2_2") (pintype "passive"))
      (node (ref "C13") (pin "2") (pinfunction "2_2") (pintype "passive"))
      (node (ref "C14") (pin "2") (pinfunction "2_2") (pintype "passive"))
      (node (ref "C15") (pin "2") (pinfunction "2_2") (pintype "passive"))
      (node (ref "C16") (pin "2") (pinfunction "2_2") (pintype "passive"))
      (node (ref "D2") (pin "1") (pinfunction "A_1") (pintype "passive"))
      (node (ref "L2") (pin "2") (pinfunction "2_2") (pintype "passive"))
      (node (ref "Q1") (pin "1") (pinfunction "G_1") (pintype "passive"))
      (node (ref "R8") (pin "2") (pinfunction "2_2") (pintype "passive"))
      (node (ref "R9") (pin "2") (pinfunction "2_2") (pintype "passive"))
    )
    (net (code "35") (name "5V-IN") (class "Default")
      (node (ref "5V") (pin "1") (pinfunction "1_1") (pintype "passive"))
      (node (ref "CN5") (pin "3") (pinfunction "3_3") (pintype "passive"))
      (node (ref "D2") (pin "2") (pinfunction "K_2") (pintype "passive"))
      (node (ref "Q1") (pin "3") (pinfunction "D_3") (pintype "passive"))
      (node (ref "Q2") (pin "2") (pinfunction "S_2") (pintype "passive"))
      (node (ref "Q3") (pin "2") (pinfunction "E_2") (pintype "passive"))
      (node (ref "R1") (pin "2") (pinfunction "2_2") (pintype "passive"))
      (node (ref "R2") (pin "1") (pinfunction "1_1") (pintype "passive"))
      (node (ref "R3") (pin "2") (pinfunction "2_2") (pintype "passive"))
    )
    (net (code "36") (name "24V") (class "Default")
      (node (ref "24V") (pin "1") (pinfunction "1_1") (pintype "passive"))
      (node (ref "C10") (pin "2") (pinfunction "2_2") (pintype "passive"))
      (node (ref "C11") (pin "2") (pinfunction "2_2") (pintype "passive"))
      (node (ref "C9") (pin "2") (pinfunction "2_2") (pintype "passive"))
      (node (ref "D7") (pin "2") (pinfunction "2_2") (pintype "passive"))
      (node (ref "P1") (pin "1") (pinfunction "+_1") (pintype "passive"))
      (node (ref "U2") (pin "8") (pinfunction "VIN_8") (pintype "passive"))
    )
    (net (code "37") (name "GND") (class "Default")
      (node (ref "BAT") (pin "1") (pinfunction "1_1") (pintype "passive"))
      (node (ref "C1") (pin "2") (pinfunction "2_2") (pintype "passive"))
      (node (ref "C10") (pin "1") (pinfunction "1_1") (pintype "passive"))
      (node (ref "C12") (pin "1") (pinfunction "1_1") (pintype "passive"))
      (node (ref "C13") (pin "1") (pinfunction "1_1") (pintype "passive"))
      (node (ref "C14") (pin "1") (pinfunction "1_1") (pintype "passive"))
      (node (ref "C15") (pin "1") (pinfunction "1_1") (pintype "passive"))
      (node (ref "C16") (pin "1") (pinfunction "1_1") (pintype "passive"))
      (node (ref "C17") (pin "1") (pinfunction "1_1") (pintype "passive"))
      (node (ref "C18") (pin "1") (pinfunction "1_1") (pintype "passive"))
      (node (ref "C19") (pin "1") (pinfunction "1_1") (pintype "passive"))
      (node (ref "C2") (pin "2") (pinfunction "2_2") (pintype "passive"))
      (node (ref "C20") (pin "1") (pinfunction "1_1") (pintype "passive"))
      (node (ref "C21") (pin "1") (pinfunction "1_1") (pintype "passive"))
      (node (ref "C22") (pin "1") (pinfunction "1_1") (pintype "passive"))
      (node (ref "C23") (pin "1") (pinfunction "1_1") (pintype "passive"))
      (node (ref "C25") (pin "1") (pinfunction "1_1") (pintype "passive"))
      (node (ref "C26") (pin "1") (pinfunction "1_1") (pintype "passive"))
      (node (ref "C27") (pin "1") (pinfunction "1_1") (pintype "passive"))
      (node (ref "C28") (pin "1") (pinfunction "1_1") (pintype "passive"))
      (node (ref "C29") (pin "1") (pinfunction "1_1") (pintype "passive"))
      (node (ref "C3") (pin "2") (pinfunction "2_2") (pintype "passive"))
      (node (ref "C30") (pin "1") (pinfunction "1_1") (pintype "passive"))
      (node (ref "C31") (pin "1") (pinfunction "1_1") (pintype "passive"))
      (node (ref "C32") (pin "1") (pinfunction "1_1") (pintype "passive"))
      (node (ref "C33") (pin "1") (pinfunction "1_1") (pintype "passive"))
      (node (ref "C34") (pin "1") (pinfunction "1_1") (pintype "passive"))
      (node (ref "C35") (pin "1") (pinfunction "1_1") (pintype "passive"))
      (node (ref "C36") (pin "1") (pinfunction "1_1") (pintype "passive"))
      (node (ref "C37") (pin "1") (pinfunction "1_1") (pintype "passive"))
      (node (ref "C38") (pin "1") (pinfunction "1_1") (pintype "passive"))
      (node (ref "C39") (pin "1") (pinfunction "1_1") (pintype "passive"))
      (node (ref "C4") (pin "2") (pinfunction "2_2") (pintype "passive"))
      (node (ref "C40") (pin "1") (pinfunction "1_1") (pintype "passive"))
      (node (ref "C41") (pin "1") (pinfunction "1_1") (pintype "passive"))
      (node (ref "C42") (pin "1") (pinfunction "1_1") (pintype "passive"))
      (node (ref "C43") (pin "1") (pinfunction "1_1") (pintype "passive"))
      (node (ref "C44") (pin "1") (pinfunction "1_1") (pintype "passive"))
      (node (ref "C45") (pin "1") (pinfunction "1_1") (pintype "passive"))
      (node (ref "C46") (pin "1") (pinfunction "1_1") (pintype "passive"))
      (node (ref "C47") (pin "1") (pinfunction "1_1") (pintype "passive"))
      (node (ref "C48") (pin "1") (pinfunction "1_1") (pintype "passive"))
      (node (ref "C49") (pin "1") (pinfunction "1_1") (pintype "passive"))
      (node (ref "C5") (pin "1") (pinfunction "1_1") (pintype "passive"))
      (node (ref "C50") (pin "1") (pinfunction "1_1") (pintype "passive"))
      (node (ref "C51") (pin "2") (pinfunction "2_2") (pintype "passive"))
      (node (ref "C52") (pin "2") (pinfunction "2_2") (pintype "passive"))
      (node (ref "C53") (pin "2") (pinfunction "2_2") (pintype "passive"))
      (node (ref "C54") (pin "2") (pinfunction "2_2") (pintype "passive"))
      (node (ref "C55") (pin "1") (pinfunction "1_1") (pintype "passive"))
      (node (ref "C56") (pin "2") (pinfunction "2_2") (pintype "passive"))
      (node (ref "C6") (pin "1") (pinfunction "1_1") (pintype "passive"))
      (node (ref "C7") (pin "1") (pinfunction "1_1") (pintype "passive"))
      (node (ref "C8") (pin "1") (pinfunction "1_1") (pintype "passive"))
      (node (ref "C9") (pin "1") (pinfunction "1_1") (pintype "passive"))
      (node (ref "CN5") (pin "1") (pinfunction "1_1") (pintype "passive"))
      (node (ref "D7") (pin "1") (pinfunction "1_1") (pintype "passive"))
      (node (ref "D8") (pin "1") (pinfunction "A_1") (pintype "passive"))
      (node (ref "D9") (pin "1") (pinfunction "1_1") (pintype "passive"))
      (node (ref "D9") (pin "2") (pinfunction "2_2") (pintype "passive"))
      (node (ref "GND") (pin "1") (pinfunction "1_1") (pintype "passive"))
      (node (ref "LED") (pin "3") (pinfunction "3_3") (pintype "passive"))
      (node (ref "LED") (pin "4") (pinfunction "4_4") (pintype "passive"))
      (node (ref "P1") (pin "2") (pinfunction "--_2") (pintype "passive"))
      (node (ref "P2") (pin "2") (pinfunction "2_2") (pintype "passive"))
      (node (ref "P3") (pin "3") (pinfunction "3_3") (pintype "passive"))
      (node (ref "Q5") (pin "2") (pinfunction "E_2") (pintype "passive"))
      (node (ref "Q6") (pin "2") (pinfunction "S_2") (pintype "passive"))
      (node (ref "Q7") (pin "2") (pinfunction "S_2") (pintype "passive"))
      (node (ref "Q8") (pin "2") (pinfunction "S_2") (pintype "passive"))
      (node (ref "R10") (pin "1") (pinfunction "1_1") (pintype "passive"))
      (node (ref "R11") (pin "1") (pinfunction "1_1") (pintype "passive"))
      (node (ref "R13") (pin "2") (pinfunction "2_2") (pintype "passive"))
      (node (ref "R21") (pin "2") (pinfunction "2_2") (pintype "passive"))
      (node (ref "R24") (pin "2") (pinfunction "2_2") (pintype "passive"))
      (node (ref "R30") (pin "1") (pinfunction "1_1") (pintype "passive"))
      (node (ref "R31") (pin "1") (pinfunction "1_1") (pintype "passive"))
      (node (ref "R32") (pin "1") (pinfunction "1_1") (pintype "passive"))
      (node (ref "R36") (pin "2") (pinfunction "2_2") (pintype "passive"))
      (node (ref "R9") (pin "1") (pinfunction "1_1") (pintype "passive"))
      (node (ref "S3") (pin "2") (pinfunction "2_2") (pintype "passive"))
      (node (ref "SW2") (pin "3") (pinfunction "3_3") (pintype "passive"))
      (node (ref "SW2") (pin "4") (pinfunction "4_4") (pintype "passive"))
      (node (ref "SW4") (pin "2") (pinfunction "2_2") (pintype "passive"))
      (node (ref "U1") (pin "9") (pinfunction "EP_9") (pintype "passive"))
      (node (ref "U2") (pin "3") (pinfunction "GND_3") (pintype "passive"))
      (node (ref "U2") (pin "5") (pinfunction "CS_5") (pintype "passive"))
      (node (ref "U3") (pin "23") (pinfunction "VSS_1_23") (pintype "power_in"))
      (node (ref "U3") (pin "35") (pinfunction "VSS_2_35") (pintype "power_in"))
      (node (ref "U3") (pin "47") (pinfunction "VSS_3_47") (pintype "power_in"))
      (node (ref "U3") (pin "8") (pinfunction "VSSA_8") (pintype "power_in"))
      (node (ref "U4") (pin "10") (pinfunction "INPB_10") (pintype "passive"))
      (node (ref "U4") (pin "14") (pinfunction "XI_14") (pintype "passive"))
      (node (ref "U4") (pin "5") (pinfunction "AGND_5") (pintype "passive"))
      (node (ref "U4") (pin "9") (pinfunction "INNB_9") (pintype "passive"))
      (node (ref "U5") (pin "2") (pinfunction "GND_2") (pintype "passive"))
      (node (ref "U5") (pin "8") (pinfunction "S_8") (pintype "passive"))
      (node (ref "USB") (pin "5") (pinfunction "GND_5") (pintype "passive"))
      (node (ref "USB2") (pin "4") (pinfunction "GND_4") (pintype "passive"))
      (node (ref "VR1") (pin "1") (pinfunction "GND_1") (pintype "passive"))
      (node (ref "VR2") (pin "1") (pinfunction "GND_1") (pintype "passive"))
      (node (ref "VR3") (pin "1") (pinfunction "GND_1") (pintype "passive"))
      (node (ref "VR4") (pin "1") (pinfunction "GND_1") (pintype "passive"))
      (node (ref "VR5") (pin "1") (pinfunction "GND_1") (pintype "passive"))
    )
    (net (code "38") (name "Net-(C8-Pad2)") (class "Default")
      (node (ref "C8") (pin "2") (pinfunction "2_2") (pintype "passive"))
      (node (ref "R4") (pin "1") (pinfunction "1_1") (pintype "passive"))
    )
    (net (code "39") (name "Net-(D1-A)") (class "Default")
      (node (ref "C1") (pin "1") (pinfunction "1_1") (pintype "passive"))
      (node (ref "C2") (pin "1") (pinfunction "1_1") (pintype "passive"))
      (node (ref "C3") (pin "1") (pinfunction "1_1") (pintype "passive"))
      (node (ref "C4") (pin "1") (pinfunction "1_1") (pintype "passive"))
      (node (ref "D1") (pin "1") (pinfunction "A_1") (pintype "passive"))
      (node (ref "U1") (pin "8") (pinfunction "VOUT_8") (pintype "passive"))
    )
    (net (code "40") (name "Net-(D1-K)") (class "Default")
      (node (ref "D1") (pin "2") (pinfunction "K_2") (pintype "passive"))
      (node (ref "SW1") (pin "2") (pinfunction "2_2") (pintype "passive"))
    )
    (net (code "41") (name "Net-(D8-K)") (class "Default")
      (node (ref "D8") (pin "2") (pinfunction "K_2") (pintype "passive"))
      (node (ref "R3") (pin "1") (pinfunction "1_1") (pintype "passive"))
      (node (ref "R6") (pin "1") (pinfunction "1_1") (pintype "passive"))
    )
    (net (code "42") (name "Net-(P2-Pad3)") (class "Default")
      (node (ref "P2") (pin "3") (pinfunction "3_3") (pintype "passive"))
      (node (ref "R34") (pin "1") (pinfunction "1_1") (pintype "passive"))
    )
    (net (code "43") (name "Net-(P2-Pad4)") (class "Default")
      (node (ref "P2") (pin "4") (pinfunction "4_4") (pintype "passive"))
      (node (ref "R33") (pin "1") (pinfunction "1_1") (pintype "passive"))
    )
    (net (code "44") (name "Net-(P3-Pad1)") (class "Default")
      (node (ref "P3") (pin "1") (pinfunction "1_1") (pintype "passive"))
      (node (ref "R29") (pin "1") (pinfunction "1_1") (pintype "passive"))
    )
    (net (code "45") (name "Net-(Q2-D)") (class "Default")
      (node (ref "F1") (pin "1") (pinfunction "1_1") (pintype "passive"))
      (node (ref "Q2") (pin "3") (pinfunction "D_3") (pintype "passive"))
      (node (ref "R2") (pin "2") (pinfunction "2_2") (pintype "passive"))
    )
    (net (code "46") (name "Net-(Q2-G)") (class "Default")
      (node (ref "Q2") (pin "1") (pinfunction "G_1") (pintype "passive"))
      (node (ref "Q3") (pin "3") (pinfunction "C_3") (pintype "passive"))
      (node (ref "R10") (pin "2") (pinfunction "2_2") (pintype "passive"))
    )
    (net (code "47") (name "Net-(Q3-B)") (class "Default")
      (node (ref "Q3") (pin "1") (pinfunction "B_1") (pintype "passive"))
      (node (ref "R6") (pin "2") (pinfunction "2_2") (pintype "passive"))
    )
    (net (code "48") (name "Net-(Q4-B)") (class "Default")
      (node (ref "Q4") (pin "1") (pinfunction "B_1") (pintype "passive"))
      (node (ref "U4") (pin "2") (pinfunction "BASE_2") (pintype "passive"))
    )
    (net (code "49") (name "Net-(Q5-B)") (class "Default")
      (node (ref "Q5") (pin "1") (pinfunction "B_1") (pintype "passive"))
      (node (ref "R29") (pin "2") (pinfunction "2_2") (pintype "passive"))
    )
    (net (code "50") (name "Net-(Q6-D)") (class "Default")
      (node (ref "Q6") (pin "3") (pinfunction "D_3") (pintype "passive"))
      (node (ref "R26") (pin "1") (pinfunction "1_1") (pintype "passive"))
    )
    (net (code "51") (name "Net-(Q7-D)") (class "Default")
      (node (ref "Q7") (pin "3") (pinfunction "D_3") (pintype "passive"))
      (node (ref "R27") (pin "1") (pinfunction "1_1") (pintype "passive"))
    )
    (net (code "52") (name "Net-(Q8-D)") (class "Default")
      (node (ref "Q8") (pin "3") (pinfunction "D_3") (pintype "passive"))
      (node (ref "R28") (pin "1") (pinfunction "1_1") (pintype "passive"))
    )
    (net (code "53") (name "Net-(R7-Pad1)") (class "Default")
      (node (ref "R7") (pin "1") (pinfunction "1_1") (pintype "passive"))
      (node (ref "SW2") (pin "1") (pinfunction "1_1") (pintype "passive"))
      (node (ref "SW2") (pin "2") (pinfunction "2_2") (pintype "passive"))
    )
    (net (code "54") (name "Net-(U1-BAT)") (class "Default")
      (node (ref "C7") (pin "2") (pinfunction "2_2") (pintype "passive"))
      (node (ref "R5") (pin "1") (pinfunction "1_1") (pintype "passive"))
      (node (ref "U1") (pin "6") (pinfunction "BAT_6") (pintype "passive"))
    )
    (net (code "55") (name "Net-(U1-KEY)") (class "Default")
      (node (ref "R7") (pin "2") (pinfunction "2_2") (pintype "passive"))
      (node (ref "U1") (pin "5") (pinfunction "KEY_5") (pintype "passive"))
    )
    (net (code "56") (name "Net-(U1-LED1)") (class "Default")
      (node (ref "D3") (pin "A") (pinfunction "A_A") (pintype "passive"))
      (node (ref "D4") (pin "K") (pinfunction "K_K") (pintype "passive"))
      (node (ref "U1") (pin "2") (pinfunction "LED1_2") (pintype "passive"))
    )
    (net (code "57") (name "Net-(U1-LED2)") (class "Default")
      (node (ref "D5") (pin "A") (pinfunction "A_A") (pintype "passive"))
      (node (ref "D6") (pin "K") (pinfunction "K_K") (pintype "passive"))
      (node (ref "U1") (pin "3") (pinfunction "LED2_3") (pintype "passive"))
    )
    (net (code "58") (name "Net-(U1-LED3)") (class "Default")
      (node (ref "D3") (pin "K") (pinfunction "K_K") (pintype "passive"))
      (node (ref "D4") (pin "A") (pinfunction "A_A") (pintype "passive"))
      (node (ref "D5") (pin "K") (pinfunction "K_K") (pintype "passive"))
      (node (ref "D6") (pin "A") (pinfunction "A_A") (pintype "passive"))
      (node (ref "U1") (pin "4") (pinfunction "LED3_4") (pintype "passive"))
    )
    (net (code "59") (name "Net-(U1-SW)") (class "Default")
      (node (ref "L1") (pin "1") (pinfunction "1_1") (pintype "passive"))
      (node (ref "U1") (pin "7") (pinfunction "SW_7") (pintype "passive"))
    )
    (net (code "60") (name "Net-(U1-VIN)") (class "Default")
      (node (ref "C5") (pin "2") (pinfunction "2_2") (pintype "passive"))
      (node (ref "R4") (pin "2") (pinfunction "2_2") (pintype "passive"))
      (node (ref "U1") (pin "1") (pinfunction "VIN_1") (pintype "passive"))
      (node (ref "USB") (pin "1") (pinfunction "VCC_1") (pintype "passive"))
    )
    (net (code "61") (name "Net-(U2-EP)") (class "Default")
      (node (ref "D9") (pin "3") (pinfunction "3_3") (pintype "passive"))
      (node (ref "L2") (pin "1") (pinfunction "1_1") (pintype "passive"))
      (node (ref "U2") (pin "2") (pinfunction "SW_2") (pintype "passive"))
      (node (ref "U2") (pin "9") (pinfunction "EP_9") (pintype "passive"))
    )
    (net (code "62") (name "Net-(U2-FB)") (class "Default")
      (node (ref "R11") (pin "2") (pinfunction "2_2") (pintype "passive"))
      (node (ref "R8") (pin "1") (pinfunction "1_1") (pintype "passive"))
      (node (ref "U2") (pin "4") (pinfunction "FB_4") (pintype "passive"))
    )
    (net (code "63") (name "Net-(U2-VC)") (class "Default")
      (node (ref "C11") (pin "1") (pinfunction "1_1") (pintype "passive"))
      (node (ref "U2") (pin "7") (pinfunction "VC_7") (pintype "passive"))
    )
    (net (code "64") (name "Net-(U3B-VDDA)") (class "Default")
      (node (ref "C45") (pin "2") (pinfunction "2_2") (pintype "passive"))
      (node (ref "C46") (pin "2") (pinfunction "2_2") (pintype "passive"))
      (node (ref "L3") (pin "2") (pinfunction "2_2") (pintype "passive"))
      (node (ref "U3") (pin "9") (pinfunction "VDDA_9") (pintype "power_in"))
    )
    (net (code "65") (name "Net-(U4-INNA)") (class "Default")
      (node (ref "C24") (pin "1") (pinfunction "1_1") (pintype "passive"))
      (node (ref "R16") (pin "1") (pinfunction "1_1") (pintype "passive"))
      (node (ref "U4") (pin "7") (pinfunction "INNA_7") (pintype "passive"))
    )
    (net (code "66") (name "Net-(U4-INPA)") (class "Default")
      (node (ref "C24") (pin "2") (pinfunction "2_2") (pintype "passive"))
      (node (ref "R14") (pin "1") (pinfunction "1_1") (pintype "passive"))
      (node (ref "U4") (pin "8") (pinfunction "INPA_8") (pintype "passive"))
    )
    (net (code "67") (name "Net-(U4-RATE)") (class "Default")
      (node (ref "R35") (pin "2") (pinfunction "2_2") (pintype "passive"))
      (node (ref "R36") (pin "1") (pinfunction "1_1") (pintype "passive"))
      (node (ref "U4") (pin "15") (pinfunction "RATE_15") (pintype "passive"))
    )
    (net (code "68") (name "Net-(U4-VBG)") (class "Default")
      (node (ref "C23") (pin "2") (pinfunction "2_2") (pintype "passive"))
      (node (ref "U4") (pin "6") (pinfunction "VBG_6") (pintype "passive"))
    )
    (net (code "69") (name "Net-(U4-VFB)") (class "Default")
      (node (ref "R12") (pin "1") (pinfunction "1_1") (pintype "passive"))
      (node (ref "R13") (pin "1") (pinfunction "1_1") (pintype "passive"))
      (node (ref "U4") (pin "4") (pinfunction "VFB_4") (pintype "passive"))
    )
    (net (code "70") (name "Net-(U5-CANH)") (class "Default")
      (node (ref "L4") (pin "1") (pinfunction "1_1") (pintype "passive"))
      (node (ref "R23") (pin "2") (pinfunction "2_2") (pintype "passive"))
      (node (ref "U5") (pin "7") (pinfunction "CANH_7") (pintype "passive"))
    )
    (net (code "71") (name "Net-(U5-CANL)") (class "Default")
      (node (ref "L4") (pin "2") (pinfunction "2_2") (pintype "passive"))
      (node (ref "R23") (pin "1") (pinfunction "1_1") (pintype "passive"))
      (node (ref "U5") (pin "6") (pinfunction "CANL_6") (pintype "passive"))
    )
    (net (code "72") (name "Net-(VR2-Vout)") (class "Default")
      (node (ref "C25") (pin "2") (pinfunction "2_2") (pintype "passive"))
      (node (ref "C28") (pin "2") (pinfunction "2_2") (pintype "passive"))
      (node (ref "R15") (pin "1") (pinfunction "1_1") (pintype "passive"))
      (node (ref "VR2") (pin "2") (pinfunction "Vout_2") (pintype "passive"))
    )
    (net (code "73") (name "Net-(VR3-Vout)") (class "Default")
      (node (ref "C31") (pin "2") (pinfunction "2_2") (pintype "passive"))
      (node (ref "C32") (pin "2") (pinfunction "2_2") (pintype "passive"))
      (node (ref "R17") (pin "1") (pinfunction "1_1") (pintype "passive"))
      (node (ref "VR3") (pin "2") (pinfunction "Vout_2") (pintype "passive"))
    )
    (net (code "74") (name "Net-(VR4-Vout)") (class "Default")
      (node (ref "C43") (pin "2") (pinfunction "2_2") (pintype "passive"))
      (node (ref "C44") (pin "2") (pinfunction "2_2") (pintype "passive"))
      (node (ref "R18") (pin "1") (pinfunction "1_1") (pintype "passive"))
      (node (ref "VR4") (pin "2") (pinfunction "Vout_2") (pintype "passive"))
    )
    (net (code "75") (name "Net-(VR5-Vout)") (class "Default")
      (node (ref "C49") (pin "2") (pinfunction "2_2") (pintype "passive"))
      (node (ref "C50") (pin "2") (pinfunction "2_2") (pintype "passive"))
      (node (ref "R19") (pin "1") (pinfunction "1_1") (pintype "passive"))
      (node (ref "VR5") (pin "2") (pinfunction "Vout_2") (pintype "passive"))
    )
    (net (code "76") (name "S1-R(E+)") (class "Default")
      (node (ref "C22") (pin "2") (pinfunction "2_2") (pintype "passive"))
      (node (ref "Q4") (pin "3") (pinfunction "C_3") (pintype "passive"))
      (node (ref "R12") (pin "2") (pinfunction "2_2") (pintype "passive"))
      (node (ref "S1") (pin "2") (pinfunction "2_2") (pintype "passive"))
      (node (ref "U4") (pin "3") (pinfunction "AVDD_3") (pintype "passive"))
    )
    (net (code "77") (name "VBAT(3.7V)") (class "Default")
      (node (ref "3.7-4.2V") (pin "1") (pinfunction "1_1") (pintype "passive"))
      (node (ref "BAT") (pin "2") (pinfunction "2_2") (pintype "passive"))
      (node (ref "C6") (pin "2") (pinfunction "2_2") (pintype "passive"))
      (node (ref "L1") (pin "2") (pinfunction "2_2") (pintype "passive"))
      (node (ref "R5") (pin "2") (pinfunction "2_2") (pintype "passive"))
    )
    (net (code "78") (name "unconnected-(BAT-Pad3)") (class "Default")
      (node (ref "BAT") (pin "3") (pinfunction "3_3") (pintype "passive+no_connect"))
    )
    (net (code "79") (name "unconnected-(BAT-Pad4)") (class "Default")
      (node (ref "BAT") (pin "4") (pinfunction "4_4") (pintype "passive+no_connect"))
    )
    (net (code "80") (name "unconnected-(CAN-Pad3)") (class "Default")
      (node (ref "CAN") (pin "3") (pinfunction "3_3") (pintype "passive+no_connect"))
    )
    (net (code "81") (name "unconnected-(CAN-Pad4)") (class "Default")
      (node (ref "CAN") (pin "4") (pinfunction "4_4") (pintype "passive+no_connect"))
    )
    (net (code "82") (name "unconnected-(CN5-Pad4)") (class "Default")
      (node (ref "CN5") (pin "4") (pinfunction "4_4") (pintype "passive+no_connect"))
    )
    (net (code "83") (name "unconnected-(CN5-Pad5)") (class "Default")
      (node (ref "CN5") (pin "5") (pinfunction "5_5") (pintype "passive+no_connect"))
    )
    (net (code "84") (name "unconnected-(LEDL-Pad5)") (class "Default")
      (node (ref "LEDL") (pin "5") (pinfunction "5_5") (pintype "passive+no_connect"))
    )
    (net (code "85") (name "unconnected-(LEDL-Pad6)") (class "Default")
      (node (ref "LEDL") (pin "6") (pinfunction "6_6") (pintype "passive+no_connect"))
    )
    (net (code "86") (name "unconnected-(LEDR-Pad5)") (class "Default")
      (node (ref "LEDR") (pin "5") (pinfunction "5_5") (pintype "passive+no_connect"))
    )
    (net (code "87") (name "unconnected-(LEDR-Pad6)") (class "Default")
      (node (ref "LEDR") (pin "6") (pinfunction "6_6") (pintype "passive+no_connect"))
    )
    (net (code "88") (name "unconnected-(S1-Pad4)") (class "Default")
      (node (ref "S1") (pin "4") (pinfunction "4_4") (pintype "passive+no_connect"))
    )
    (net (code "89") (name "unconnected-(S1-Pad5)") (class "Default")
      (node (ref "S1") (pin "5") (pinfunction "5_5") (pintype "passive+no_connect"))
    )
    (net (code "90") (name "unconnected-(S2-Pad4)") (class "Default")
      (node (ref "S2") (pin "4") (pinfunction "4_4") (pintype "passive+no_connect"))
    )
    (net (code "91") (name "unconnected-(S2-Pad5)") (class "Default")
      (node (ref "S2") (pin "5") (pinfunction "5_5") (pintype "passive+no_connect"))
    )
    (net (code "92") (name "unconnected-(S3-Pad4)") (class "Default")
      (node (ref "S3") (pin "4") (pinfunction "4_4") (pintype "passive+no_connect"))
    )
    (net (code "93") (name "unconnected-(S3-Pad5)") (class "Default")
      (node (ref "S3") (pin "5") (pinfunction "5_5") (pintype "passive+no_connect"))
    )
    (net (code "94") (name "unconnected-(S4-Pad4)") (class "Default")
      (node (ref "S4") (pin "4") (pinfunction "4_4") (pintype "passive+no_connect"))
    )
    (net (code "95") (name "unconnected-(S4-Pad5)") (class "Default")
      (node (ref "S4") (pin "5") (pinfunction "5_5") (pintype "passive+no_connect"))
    )
    (net (code "96") (name "unconnected-(SW1-Pad1)") (class "Default")
      (node (ref "SW1") (pin "1") (pinfunction "1_1") (pintype "passive+no_connect"))
    )
    (net (code "97") (name "unconnected-(U2-NC-Pad1)") (class "Default")
      (node (ref "U2") (pin "1") (pinfunction "NC_1") (pintype "passive"))
    )
    (net (code "98") (name "unconnected-(U2-NC-Pad6)") (class "Default")
      (node (ref "U2") (pin "6") (pinfunction "NC_6") (pintype "passive"))
    )
    (net (code "99") (name "unconnected-(U3A-PA0-WKUP-Pad10)") (class "Default")
      (node (ref "U3") (pin "10") (pinfunction "PA0-WKUP_10") (pintype "bidirectional+no_connect"))
    )
    (net (code "100") (name "unconnected-(U3A-PA1-Pad11)") (class "Default")
      (node (ref "U3") (pin "11") (pinfunction "PA1_11") (pintype "bidirectional+no_connect"))
    )
    (net (code "101") (name "unconnected-(U3A-PA2-Pad12)") (class "Default")
      (node (ref "U3") (pin "12") (pinfunction "PA2_12") (pintype "bidirectional+no_connect"))
    )
    (net (code "102") (name "unconnected-(U3A-PA3-Pad13)") (class "Default")
      (node (ref "U3") (pin "13") (pinfunction "PA3_13") (pintype "bidirectional+no_connect"))
    )
    (net (code "103") (name "unconnected-(U3A-PA4-Pad14)") (class "Default")
      (node (ref "U3") (pin "14") (pinfunction "PA4_14") (pintype "bidirectional+no_connect"))
    )
    (net (code "104") (name "unconnected-(U3A-PA8-Pad29)") (class "Default")
      (node (ref "U3") (pin "29") (pinfunction "PA8_29") (pintype "bidirectional+no_connect"))
    )
    (net (code "105") (name "unconnected-(U3A-PA9-Pad30)") (class "Default")
      (node (ref "U3") (pin "30") (pinfunction "PA9_30") (pintype "bidirectional+no_connect"))
    )
    (net (code "106") (name "unconnected-(U3A-PA10-Pad31)") (class "Default")
      (node (ref "U3") (pin "31") (pinfunction "PA10_31") (pintype "bidirectional+no_connect"))
    )
    (net (code "107") (name "unconnected-(U3A-PA15-Pad38)") (class "Default")
      (node (ref "U3") (pin "38") (pinfunction "PA15_38") (pintype "bidirectional+no_connect"))
    )
    (net (code "108") (name "unconnected-(U3A-PB3-Pad39)") (class "Default")
      (node (ref "U3") (pin "39") (pinfunction "PB3_39") (pintype "bidirectional+no_connect"))
    )
    (net (code "109") (name "unconnected-(U3A-PB4-Pad40)") (class "Default")
      (node (ref "U3") (pin "40") (pinfunction "PB4_40") (pintype "bidirectional+no_connect"))
    )
    (net (code "110") (name "unconnected-(U3A-PB5-Pad41)") (class "Default")
      (node (ref "U3") (pin "41") (pinfunction "PB5_41") (pintype "bidirectional+no_connect"))
    )
    (net (code "111") (name "unconnected-(U3A-PB6-Pad42)") (class "Default")
      (node (ref "U3") (pin "42") (pinfunction "PB6_42") (pintype "bidirectional"))
    )
    (net (code "112") (name "unconnected-(U3A-PB10-Pad21)") (class "Default")
      (node (ref "U3") (pin "21") (pinfunction "PB10_21") (pintype "bidirectional+no_connect"))
    )
    (net (code "113") (name "unconnected-(U3A-PB11-Pad22)") (class "Default")
      (node (ref "U3") (pin "22") (pinfunction "PB11_22") (pintype "bidirectional+no_connect"))
    )
    (net (code "114") (name "unconnected-(U3A-PB12-Pad25)") (class "Default")
      (node (ref "U3") (pin "25") (pinfunction "PB12_25") (pintype "bidirectional+no_connect"))
    )
    (net (code "115") (name "unconnected-(U3A-PB13-Pad26)") (class "Default")
      (node (ref "U3") (pin "26") (pinfunction "PB13_26") (pintype "bidirectional+no_connect"))
    )
    (net (code "116") (name "unconnected-(U3A-PB14-Pad27)") (class "Default")
      (node (ref "U3") (pin "27") (pinfunction "PB14_27") (pintype "bidirectional+no_connect"))
    )
    (net (code "117") (name "unconnected-(U3A-PB15-Pad28)") (class "Default")
      (node (ref "U3") (pin "28") (pinfunction "PB15_28") (pintype "bidirectional+no_connect"))
    )
    (net (code "118") (name "unconnected-(U3A-PC13-TAMPER-RTC-Pad2)") (class "Default")
      (node (ref "U3") (pin "2") (pinfunction "PC13-TAMPER-RTC_2") (pintype "bidirectional+no_connect"))
    )
    (net (code "119") (name "unconnected-(U3A-PC14-OSC32_IN-Pad3)") (class "Default")
      (node (ref "U3") (pin "3") (pinfunction "PC14-OSC32_IN_3") (pintype "bidirectional+no_connect"))
    )
    (net (code "120") (name "unconnected-(U3A-PC15-OSC32_OUT-Pad4)") (class "Default")
      (node (ref "U3") (pin "4") (pinfunction "PC15-OSC32_OUT_4") (pintype "bidirectional+no_connect"))
    )
    (net (code "121") (name "unconnected-(U4-XO-Pad13)") (class "Default")
      (node (ref "U4") (pin "13") (pinfunction "XO_13") (pintype "passive+no_connect"))
    )
    (net (code "122") (name "unconnected-(USB-D+-Pad3)") (class "Default")
      (node (ref "USB") (pin "3") (pinfunction "D+_3") (pintype "passive+no_connect"))
    )
    (net (code "123") (name "unconnected-(USB-D--Pad2)") (class "Default")
      (node (ref "USB") (pin "2") (pinfunction "D-_2") (pintype "passive+no_connect"))
    )
    (net (code "124") (name "unconnected-(USB-ID-Pad4)") (class "Default")
      (node (ref "USB") (pin "4") (pinfunction "ID_4") (pintype "passive+no_connect"))
    )
    (net (code "125") (name "unconnected-(USB-SHELL-Pad6)") (class "Default")
      (node (ref "USB") (pin "6") (pinfunction "SHELL_6") (pintype "passive+no_connect"))
    )
    (net (code "126") (name "unconnected-(USB2-D+-Pad3)") (class "Default")
      (node (ref "USB2") (pin "3") (pinfunction "D+_3") (pintype "passive+no_connect"))
    )
    (net (code "127") (name "unconnected-(USB2-D--Pad2)") (class "Default")
      (node (ref "USB2") (pin "2") (pinfunction "D-_2") (pintype "passive+no_connect"))
    )
    (net (code "128") (name "unconnected-(USB2-SHLD-Pad0)") (class "Default")
      (node (ref "USB2") (pin "0") (pinfunction "SHLD_0") (pintype "passive+no_connect"))
    )
    (net (code "129") (name "unconnected-(USB2-SHLD-Pad0)_1") (class "Default")
      (node (ref "USB2") (pin "0") (pinfunction "SHLD_0") (pintype "passive+no_connect"))
    )
  )
)
